# solderingSkillsFault.net
KiCad netlist of a schematic drawn in EAGLE
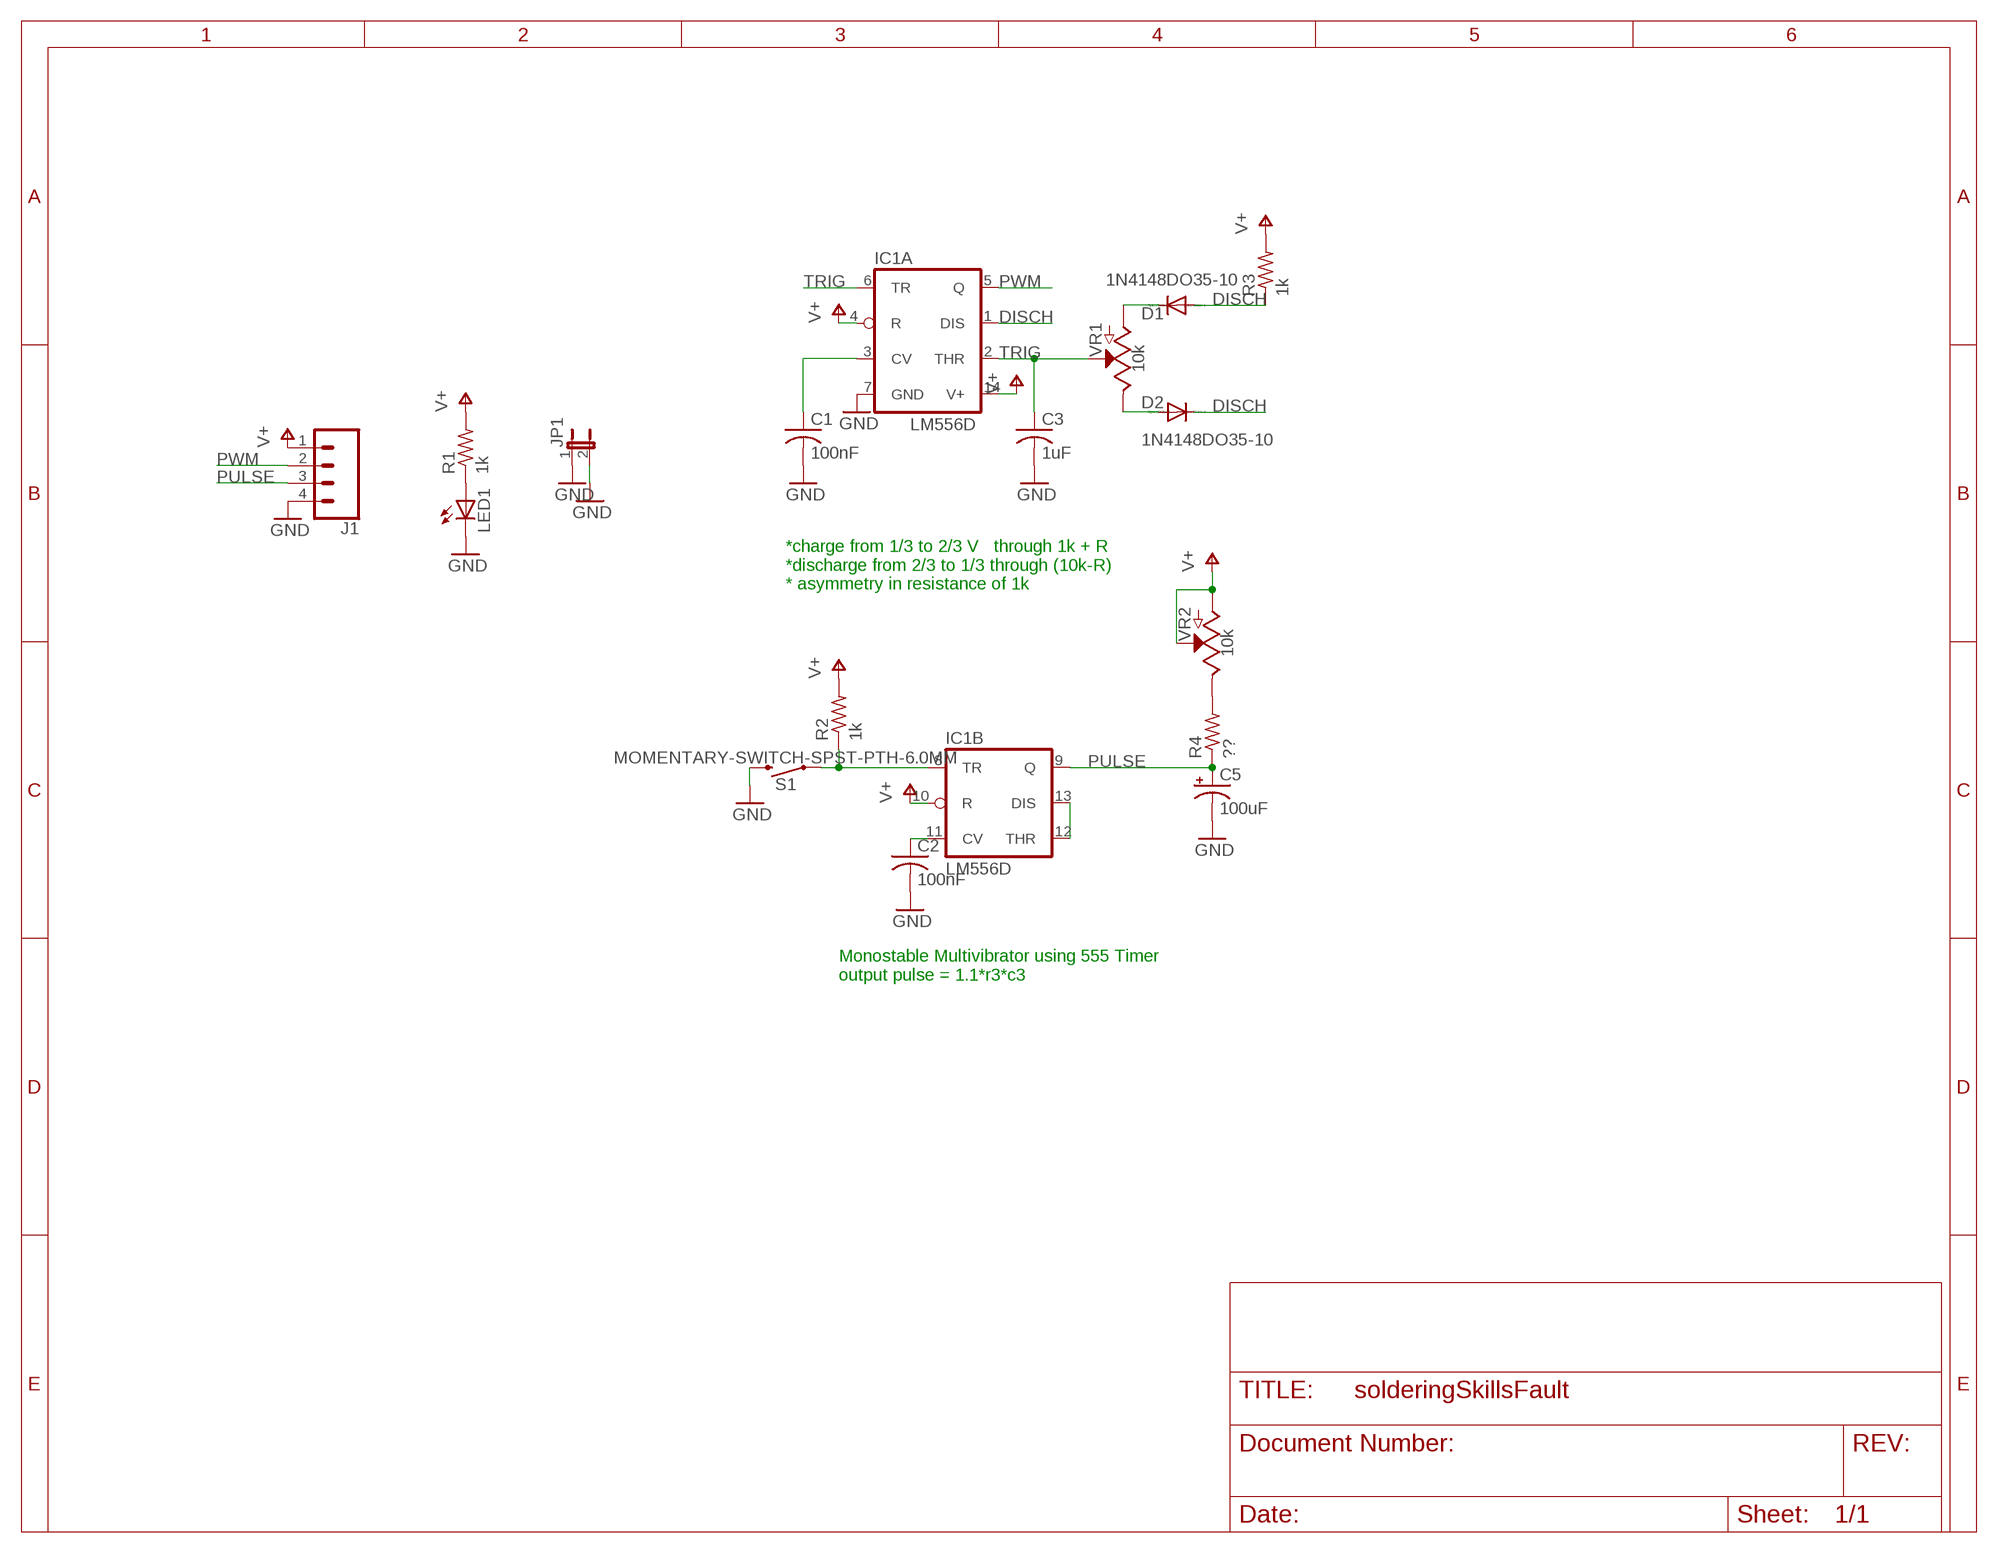
[diagram p0: schematic, sheet 1]

(export (version "E")
  (design (tool "Eeschema 10.0.6"))
  (components
    (comp (ref "C1")
      (value "100nF")
      (footprint "eagle-import:C1206")
      (libsource (lib "eagle-import") (part "C-USC1206"))
    )
    (comp (ref "C2")
      (value "100nF")
      (footprint "eagle-import:C1206")
      (libsource (lib "eagle-import") (part "C-USC1206"))
    )
    (comp (ref "C3")
      (value "1uF")
      (footprint "eagle-import:C1206")
      (libsource (lib "eagle-import") (part "C-USC1206"))
    )
    (comp (ref "C5")
      (value "100uF")
      (footprint "eagle-import:PANASONIC_C")
      (libsource (lib "eagle-import") (part "CPOL-USC"))
    )
    (comp (ref "D1")
      (value "1N4148DO35-10")
      (footprint "eagle-import:DO35-10")
      (libsource (lib "eagle-import") (part "1N4148DO35-10"))
    )
    (comp (ref "D2")
      (value "1N4148DO35-10")
      (footprint "eagle-import:DO35-10")
      (libsource (lib "eagle-import") (part "1N4148DO35-10"))
    )
    (comp (ref "IC1")
      (value "LM556D")
      (footprint "eagle-import:SO14")
      (libsource (lib "eagle-import") (part "556DLM"))
    )
    (comp (ref "J1")
      (value "CONN_04LOCK_LONGPADS")
      (footprint "eagle-import:1X04_LOCK_LONGPADS")
      (libsource (lib "eagle-import") (part "CONN_04LOCK_LONGPADS"))
    )
    (comp (ref "JP1")
      (value "JUMPER-2PTH_LOCK")
      (footprint "eagle-import:1X02_LOCK")
      (libsource (lib "eagle-import") (part "JUMPER-2PTH_LOCK"))
    )
    (comp (ref "LED1")
      (value "LEDCHIPLED_1206")
      (footprint "eagle-import:CHIPLED_1206")
      (libsource (lib "eagle-import") (part "LEDCHIPLED_1206"))
    )
    (comp (ref "R1")
      (value "1k")
      (footprint "eagle-import:M1206")
      (libsource (lib "eagle-import") (part "R-US_M1206"))
    )
    (comp (ref "R2")
      (value "1k")
      (footprint "eagle-import:M1206")
      (libsource (lib "eagle-import") (part "R-US_M1206"))
    )
    (comp (ref "R3")
      (value "1k")
      (footprint "eagle-import:M1206")
      (libsource (lib "eagle-import") (part "R-US_M1206"))
    )
    (comp (ref "R4")
      (value "??")
      (footprint "eagle-import:M1206")
      (libsource (lib "eagle-import") (part "R-US_M1206"))
    )
    (comp (ref "S1")
      (value "MOMENTARY-SWITCH-SPST-PTH-6.0MM")
      (footprint "eagle-import:TACTILE_SWITCH_PTH_6.0MM")
      (libsource (lib "eagle-import") (part "MOMENTARY-SWITCH-SPST-PTH-6.0MM"))
    )
    (comp (ref "VR1")
      (value "10k")
      (footprint "eagle-import:POT-PTH-ALPS")
      (libsource (lib "eagle-import") (part "POTENTIOMETER-PTH-9MM-1/20W-20%"))
    )
    (comp (ref "VR2")
      (value "10k")
      (footprint "eagle-import:POT-PTH-ALPS")
      (libsource (lib "eagle-import") (part "POTENTIOMETER-PTH-9MM-1/20W-20%"))
    )
  )
  (nets
    (net (code "1") (name "/DISCH") (class "Default")
      (node (ref "D1") (pin "A") (pinfunction "A_A") (pintype "passive"))
      (node (ref "D2") (pin "C") (pinfunction "C_C") (pintype "passive"))
      (node (ref "IC1") (pin "1") (pinfunction "DIS_1") (pintype "input"))
      (node (ref "R3") (pin "1") (pinfunction "1_1") (pintype "passive"))
    )
    (net (code "2") (name "/PULSE") (class "Default")
      (node (ref "C5") (pin "+") (pinfunction "+_+") (pintype "passive"))
      (node (ref "IC1") (pin "9") (pinfunction "Q_9") (pintype "output"))
      (node (ref "J1") (pin "3") (pinfunction "3_3") (pintype "passive"))
      (node (ref "R4") (pin "1") (pinfunction "1_1") (pintype "passive"))
    )
    (net (code "3") (name "/PWM") (class "Default")
      (node (ref "IC1") (pin "5") (pinfunction "Q_5") (pintype "output"))
      (node (ref "J1") (pin "2") (pinfunction "2_2") (pintype "passive"))
    )
    (net (code "4") (name "/TRIG") (class "Default")
      (node (ref "C3") (pin "1") (pinfunction "1_1") (pintype "passive"))
      (node (ref "IC1") (pin "2") (pinfunction "THR_2") (pintype "input"))
      (node (ref "IC1") (pin "6") (pinfunction "TR_6") (pintype "input"))
      (node (ref "VR1") (pin "P$2") (pinfunction "S_P$2") (pintype "passive"))
    )
    (net (code "5") (name "GND") (class "Default")
      (node (ref "C1") (pin "2") (pinfunction "2_2") (pintype "passive"))
      (node (ref "C2") (pin "2") (pinfunction "2_2") (pintype "passive"))
      (node (ref "C3") (pin "2") (pinfunction "2_2") (pintype "passive"))
      (node (ref "C5") (pin "-") (pinfunction "-_-") (pintype "passive"))
      (node (ref "IC1") (pin "7") (pinfunction "GND_7") (pintype "power_in"))
      (node (ref "J1") (pin "4") (pinfunction "4_4") (pintype "passive"))
      (node (ref "JP1") (pin "1") (pinfunction "1_1") (pintype "passive"))
      (node (ref "JP1") (pin "2") (pinfunction "2_2") (pintype "passive"))
      (node (ref "LED1") (pin "C") (pinfunction "C_C") (pintype "passive"))
      (node (ref "S1") (pin "3") (pinfunction "2_3") (pintype "passive"))
    )
    (net (code "6") (name "Net-(IC1A-CV)") (class "Default")
      (node (ref "C1") (pin "1") (pinfunction "1_1") (pintype "passive"))
      (node (ref "IC1") (pin "3") (pinfunction "CV_3") (pintype "input"))
    )
    (net (code "7") (name "Net-(IC1B-CV)") (class "Default")
      (node (ref "C2") (pin "1") (pinfunction "1_1") (pintype "passive"))
      (node (ref "IC1") (pin "11") (pinfunction "CV_11") (pintype "input"))
    )
    (net (code "8") (name "Net-(IC1B-DIS)") (class "Default")
      (node (ref "IC1") (pin "12") (pinfunction "THR_12") (pintype "input"))
      (node (ref "IC1") (pin "13") (pinfunction "DIS_13") (pintype "input"))
    )
    (net (code "9") (name "Net-(IC1B-TR)") (class "Default")
      (node (ref "IC1") (pin "8") (pinfunction "TR_8") (pintype "input"))
      (node (ref "R2") (pin "1") (pinfunction "1_1") (pintype "passive"))
      (node (ref "S1") (pin "1") (pinfunction "1_1") (pintype "passive"))
    )
    (net (code "10") (name "Net-(LED1-PadA)") (class "Default")
      (node (ref "LED1") (pin "A") (pinfunction "A_A") (pintype "passive"))
      (node (ref "R1") (pin "1") (pinfunction "1_1") (pintype "passive"))
    )
    (net (code "11") (name "Net-(VR1-A)") (class "Default")
      (node (ref "D1") (pin "C") (pinfunction "C_C") (pintype "passive"))
      (node (ref "VR1") (pin "P$3") (pinfunction "A_P$3") (pintype "passive"))
    )
    (net (code "12") (name "Net-(VR1-E)") (class "Default")
      (node (ref "D2") (pin "A") (pinfunction "A_A") (pintype "passive"))
      (node (ref "VR1") (pin "P$1") (pinfunction "E_P$1") (pintype "passive"))
    )
    (net (code "13") (name "Net-(VR2-E)") (class "Default")
      (node (ref "R4") (pin "2") (pinfunction "2_2") (pintype "passive"))
      (node (ref "VR2") (pin "P$1") (pinfunction "E_P$1") (pintype "passive"))
    )
    (net (code "14") (name "V+") (class "Default")
      (node (ref "IC1") (pin "10") (pinfunction "R_10") (pintype "input"))
      (node (ref "IC1") (pin "14") (pinfunction "V+_14") (pintype "power_in"))
      (node (ref "IC1") (pin "4") (pinfunction "R_4") (pintype "input"))
      (node (ref "J1") (pin "1") (pinfunction "1_1") (pintype "passive"))
      (node (ref "R1") (pin "2") (pinfunction "2_2") (pintype "passive"))
      (node (ref "R2") (pin "2") (pinfunction "2_2") (pintype "passive"))
      (node (ref "R3") (pin "2") (pinfunction "2_2") (pintype "passive"))
      (node (ref "VR2") (pin "P$2") (pinfunction "S_P$2") (pintype "passive"))
      (node (ref "VR2") (pin "P$3") (pinfunction "A_P$3") (pintype "passive"))
    )
  )
)
